# 05_-_AUDIO.net
KiCad netlist of a schematic drawn in Altium Designer
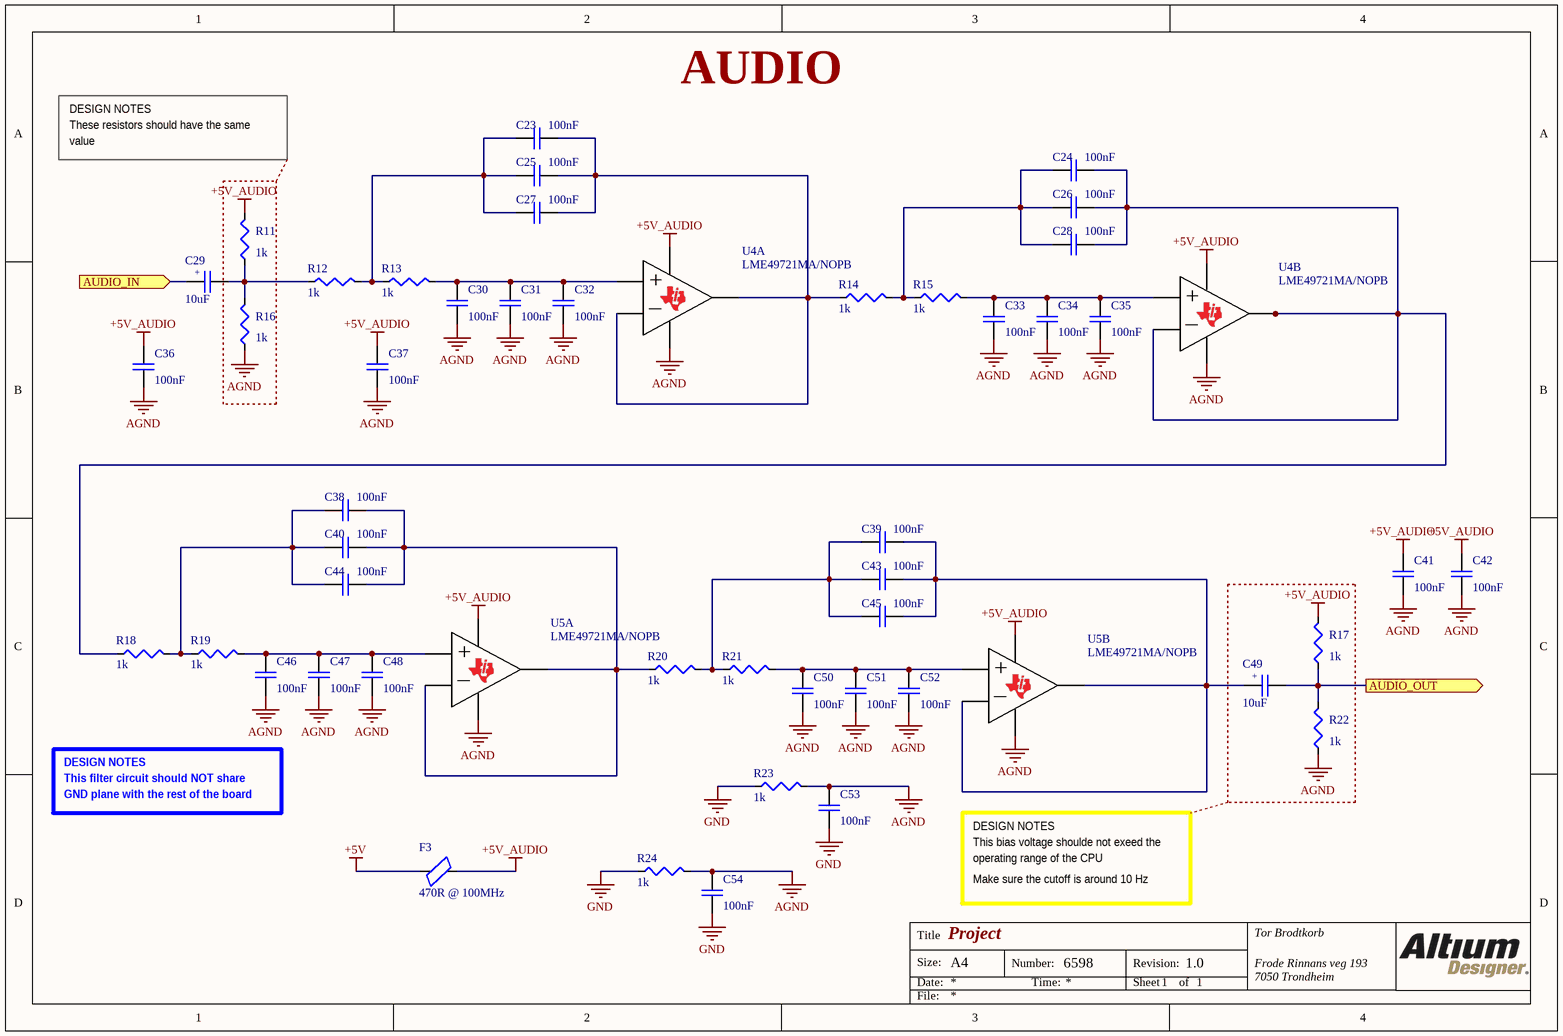
[diagram p0: [05] - AUDIO.SchDoc]

(export (version "E")
  (design (tool "Eeschema 10.0.6"))
  (components
    (comp (ref "C23")
      (value "100nF")
      (footprint "C0603")
      (description "C0603")
      (fields (field (name "Comment") "02016D104KAT2A"))
      (libsource (lib "Passive components") (part "02016D104KAT2A"))
    )
    (comp (ref "C24")
      (value "100nF")
      (footprint "C0603")
      (description "C0603")
      (fields (field (name "Comment") "02016D104KAT2A"))
      (libsource (lib "Passive components") (part "02016D104KAT2A"))
    )
    (comp (ref "C25")
      (value "100nF")
      (footprint "C0603")
      (description "C0603")
      (fields (field (name "Comment") "02016D104KAT2A"))
      (libsource (lib "Passive components") (part "02016D104KAT2A"))
    )
    (comp (ref "C26")
      (value "100nF")
      (footprint "C0603")
      (description "C0603")
      (fields (field (name "Comment") "02016D104KAT2A"))
      (libsource (lib "Passive components") (part "02016D104KAT2A"))
    )
    (comp (ref "C27")
      (value "100nF")
      (footprint "C0603")
      (description "C0603")
      (fields (field (name "Comment") "02016D104KAT2A"))
      (libsource (lib "Passive components") (part "02016D104KAT2A"))
    )
    (comp (ref "C28")
      (value "100nF")
      (footprint "C0603")
      (description "C0603")
      (fields (field (name "Comment") "02016D104KAT2A"))
      (libsource (lib "Passive components") (part "02016D104KAT2A"))
    )
    (comp (ref "C29")
      (value "10uF")
      (footprint "Capacitor electrolytic SMD 4x5.4")
      (description "El. Capacitor SMD 4x5.4")
      (fields (field (name "Comment") "EEE1HA2R2SR"))
      (libsource (lib "Passive components") (part "EEE1HA2R2SR"))
    )
    (comp (ref "C30")
      (value "100nF")
      (footprint "C0603")
      (description "C0603")
      (fields (field (name "Comment") "02016D104KAT2A"))
      (libsource (lib "Passive components") (part "02016D104KAT2A"))
    )
    (comp (ref "C31")
      (value "100nF")
      (footprint "C0603")
      (description "C0603")
      (fields (field (name "Comment") "02016D104KAT2A"))
      (libsource (lib "Passive components") (part "02016D104KAT2A"))
    )
    (comp (ref "C32")
      (value "100nF")
      (footprint "C0603")
      (description "C0603")
      (fields (field (name "Comment") "02016D104KAT2A"))
      (libsource (lib "Passive components") (part "02016D104KAT2A"))
    )
    (comp (ref "C33")
      (value "100nF")
      (footprint "C0603")
      (description "C0603")
      (fields (field (name "Comment") "02016D104KAT2A"))
      (libsource (lib "Passive components") (part "02016D104KAT2A"))
    )
    (comp (ref "C34")
      (value "100nF")
      (footprint "C0603")
      (description "C0603")
      (fields (field (name "Comment") "02016D104KAT2A"))
      (libsource (lib "Passive components") (part "02016D104KAT2A"))
    )
    (comp (ref "C35")
      (value "100nF")
      (footprint "C0603")
      (description "C0603")
      (fields (field (name "Comment") "02016D104KAT2A"))
      (libsource (lib "Passive components") (part "02016D104KAT2A"))
    )
    (comp (ref "C36")
      (value "100nF")
      (footprint "C0603")
      (description "C0603")
      (fields (field (name "Comment") "02016D104KAT2A"))
      (libsource (lib "Passive components") (part "02016D104KAT2A"))
    )
    (comp (ref "C37")
      (value "100nF")
      (footprint "C0603")
      (description "C0603")
      (fields (field (name "Comment") "02016D104KAT2A"))
      (libsource (lib "Passive components") (part "02016D104KAT2A"))
    )
    (comp (ref "C38")
      (value "100nF")
      (footprint "C0603")
      (description "C0603")
      (fields (field (name "Comment") "02016D104KAT2A"))
      (libsource (lib "Passive components") (part "02016D104KAT2A"))
    )
    (comp (ref "C39")
      (value "100nF")
      (footprint "C0603")
      (description "C0603")
      (fields (field (name "Comment") "02016D104KAT2A"))
      (libsource (lib "Passive components") (part "02016D104KAT2A"))
    )
    (comp (ref "C40")
      (value "100nF")
      (footprint "C0603")
      (description "C0603")
      (fields (field (name "Comment") "02016D104KAT2A"))
      (libsource (lib "Passive components") (part "02016D104KAT2A"))
    )
    (comp (ref "C41")
      (value "100nF")
      (footprint "C0603")
      (description "C0603")
      (fields (field (name "Comment") "02016D104KAT2A"))
      (libsource (lib "Passive components") (part "02016D104KAT2A"))
    )
    (comp (ref "C42")
      (value "100nF")
      (footprint "C0603")
      (description "C0603")
      (fields (field (name "Comment") "02016D104KAT2A"))
      (libsource (lib "Passive components") (part "02016D104KAT2A"))
    )
    (comp (ref "C43")
      (value "100nF")
      (footprint "C0603")
      (description "C0603")
      (fields (field (name "Comment") "02016D104KAT2A"))
      (libsource (lib "Passive components") (part "02016D104KAT2A"))
    )
    (comp (ref "C44")
      (value "100nF")
      (footprint "C0603")
      (description "C0603")
      (fields (field (name "Comment") "02016D104KAT2A"))
      (libsource (lib "Passive components") (part "02016D104KAT2A"))
    )
    (comp (ref "C45")
      (value "100nF")
      (footprint "C0603")
      (description "C0603")
      (fields (field (name "Comment") "02016D104KAT2A"))
      (libsource (lib "Passive components") (part "02016D104KAT2A"))
    )
    (comp (ref "C46")
      (value "100nF")
      (footprint "C0603")
      (description "C0603")
      (fields (field (name "Comment") "02016D104KAT2A"))
      (libsource (lib "Passive components") (part "02016D104KAT2A"))
    )
    (comp (ref "C47")
      (value "100nF")
      (footprint "C0603")
      (description "C0603")
      (fields (field (name "Comment") "02016D104KAT2A"))
      (libsource (lib "Passive components") (part "02016D104KAT2A"))
    )
    (comp (ref "C48")
      (value "100nF")
      (footprint "C0603")
      (description "C0603")
      (fields (field (name "Comment") "02016D104KAT2A"))
      (libsource (lib "Passive components") (part "02016D104KAT2A"))
    )
    (comp (ref "C49")
      (value "10uF")
      (footprint "Capacitor electrolytic SMD 4x5.4")
      (description "El. Capacitor SMD 4x5.4")
      (fields (field (name "Comment") "EEE1HA2R2SR"))
      (libsource (lib "Passive components") (part "EEE1HA2R2SR"))
    )
    (comp (ref "C50")
      (value "100nF")
      (footprint "C0603")
      (description "C0603")
      (fields (field (name "Comment") "02016D104KAT2A"))
      (libsource (lib "Passive components") (part "02016D104KAT2A"))
    )
    (comp (ref "C51")
      (value "100nF")
      (footprint "C0603")
      (description "C0603")
      (fields (field (name "Comment") "02016D104KAT2A"))
      (libsource (lib "Passive components") (part "02016D104KAT2A"))
    )
    (comp (ref "C52")
      (value "100nF")
      (footprint "C0603")
      (description "C0603")
      (fields (field (name "Comment") "02016D104KAT2A"))
      (libsource (lib "Passive components") (part "02016D104KAT2A"))
    )
    (comp (ref "C53")
      (value "100nF")
      (footprint "C0603")
      (description "C0603")
      (fields (field (name "Comment") "02016D104KAT2A"))
      (libsource (lib "Passive components") (part "02016D104KAT2A"))
    )
    (comp (ref "C54")
      (value "100nF")
      (footprint "C0603")
      (description "C0603")
      (fields (field (name "Comment") "02016D104KAT2A"))
      (libsource (lib "Passive components") (part "02016D104KAT2A"))
    )
    (comp (ref "F3")
      (value "470R @ 100MHz")
      (footprint "Ferrite bead 0603")
      (description "Ferrite bead 0603")
      (fields (field (name "Comment") "BLM18AG121SN1D"))
      (libsource (lib "Passive components") (part "BLM18AG121SN1D"))
    )
    (comp (ref "R11")
      (value "1k")
      (footprint "R0603")
      (description "R0603")
      (fields (field (name "Comment") "CPF-A-0603B100KE1"))
      (libsource (lib "Passive components") (part "CPF-A-0603B100KE1"))
    )
    (comp (ref "R12")
      (value "1k")
      (footprint "R0603")
      (description "R0603")
      (fields (field (name "Comment") "CPF-A-0603B100KE1"))
      (libsource (lib "Passive components") (part "CPF-A-0603B100KE1"))
    )
    (comp (ref "R13")
      (value "1k")
      (footprint "R0603")
      (description "R0603")
      (fields (field (name "Comment") "CPF-A-0603B100KE1"))
      (libsource (lib "Passive components") (part "CPF-A-0603B100KE1"))
    )
    (comp (ref "R14")
      (value "1k")
      (footprint "R0603")
      (description "R0603")
      (fields (field (name "Comment") "CPF-A-0603B100KE1"))
      (libsource (lib "Passive components") (part "CPF-A-0603B100KE1"))
    )
    (comp (ref "R15")
      (value "1k")
      (footprint "R0603")
      (description "R0603")
      (fields (field (name "Comment") "CPF-A-0603B100KE1"))
      (libsource (lib "Passive components") (part "CPF-A-0603B100KE1"))
    )
    (comp (ref "R16")
      (value "1k")
      (footprint "R0603")
      (description "R0603")
      (fields (field (name "Comment") "CPF-A-0603B100KE1"))
      (libsource (lib "Passive components") (part "CPF-A-0603B100KE1"))
    )
    (comp (ref "R17")
      (value "1k")
      (footprint "R0603")
      (description "R0603")
      (fields (field (name "Comment") "CPF-A-0603B100KE1"))
      (libsource (lib "Passive components") (part "CPF-A-0603B100KE1"))
    )
    (comp (ref "R18")
      (value "1k")
      (footprint "R0603")
      (description "R0603")
      (fields (field (name "Comment") "CPF-A-0603B100KE1"))
      (libsource (lib "Passive components") (part "CPF-A-0603B100KE1"))
    )
    (comp (ref "R19")
      (value "1k")
      (footprint "R0603")
      (description "R0603")
      (fields (field (name "Comment") "CPF-A-0603B100KE1"))
      (libsource (lib "Passive components") (part "CPF-A-0603B100KE1"))
    )
    (comp (ref "R20")
      (value "1k")
      (footprint "R0603")
      (description "R0603")
      (fields (field (name "Comment") "CPF-A-0603B100KE1"))
      (libsource (lib "Passive components") (part "CPF-A-0603B100KE1"))
    )
    (comp (ref "R21")
      (value "1k")
      (footprint "R0603")
      (description "R0603")
      (fields (field (name "Comment") "CPF-A-0603B100KE1"))
      (libsource (lib "Passive components") (part "CPF-A-0603B100KE1"))
    )
    (comp (ref "R22")
      (value "1k")
      (footprint "R0603")
      (description "R0603")
      (fields (field (name "Comment") "CPF-A-0603B100KE1"))
      (libsource (lib "Passive components") (part "CPF-A-0603B100KE1"))
    )
    (comp (ref "R23")
      (value "1k")
      (footprint "R0603")
      (description "R0603")
      (fields (field (name "Comment") "CPF-A-0603B100KE1"))
      (libsource (lib "Passive components") (part "CPF-A-0603B100KE1"))
    )
    (comp (ref "R24")
      (value "1k")
      (footprint "R0603")
      (description "R0603")
      (fields (field (name "Comment") "CPF-A-0603B100KE1"))
      (libsource (lib "Passive components") (part "CPF-A-0603B100KE1"))
    )
    (comp (ref "U4")
      (value "LME49721MA/NOPB")
      (footprint "LME49721MA/NOPB")
      (description "Audio OP amp, single supply, low voltage")
      (libsource (lib "IC") (part "LME49721MA/NOPB"))
    )
    (comp (ref "U5")
      (value "LME49721MA/NOPB")
      (footprint "LME49721MA/NOPB")
      (description "Audio OP amp, single supply, low voltage")
      (libsource (lib "IC") (part "LME49721MA/NOPB"))
    )
  )
  (nets
    (net (code "1") (name "+5V") (class "Default")
      (node (ref "F3") (pin "1") (pinfunction "1_1") (pintype "passive"))
    )
    (net (code "2") (name "+5V_AUDIO") (class "Default")
      (node (ref "C36") (pin "2") (pinfunction "2_2") (pintype "passive"))
      (node (ref "C37") (pin "2") (pinfunction "2_2") (pintype "passive"))
      (node (ref "C41") (pin "2") (pinfunction "2_2") (pintype "passive"))
      (node (ref "C42") (pin "2") (pinfunction "2_2") (pintype "passive"))
      (node (ref "F3") (pin "2") (pinfunction "2_2") (pintype "passive"))
      (node (ref "R11") (pin "2") (pinfunction "2_2") (pintype "passive"))
      (node (ref "R17") (pin "2") (pinfunction "2_2") (pintype "passive"))
      (node (ref "U4") (pin "8") (pinfunction "VDD_8") (pintype "passive"))
      (node (ref "U5") (pin "8") (pinfunction "VDD_8") (pintype "passive"))
    )
    (net (code "3") (name "/AUDIO_IN") (class "Default")
      (node (ref "C29") (pin "1") (pinfunction "1_1") (pintype "passive"))
    )
    (net (code "4") (name "/AUDIO_OUT") (class "Default")
      (node (ref "C49") (pin "2") (pinfunction "2_2") (pintype "passive"))
      (node (ref "R17") (pin "1") (pinfunction "1_1") (pintype "passive"))
      (node (ref "R22") (pin "2") (pinfunction "2_2") (pintype "passive"))
    )
    (net (code "5") (name "AGND") (class "Default")
      (node (ref "C30") (pin "1") (pinfunction "1_1") (pintype "passive"))
      (node (ref "C31") (pin "1") (pinfunction "1_1") (pintype "passive"))
      (node (ref "C32") (pin "1") (pinfunction "1_1") (pintype "passive"))
      (node (ref "C33") (pin "1") (pinfunction "1_1") (pintype "passive"))
      (node (ref "C34") (pin "1") (pinfunction "1_1") (pintype "passive"))
      (node (ref "C35") (pin "1") (pinfunction "1_1") (pintype "passive"))
      (node (ref "C36") (pin "1") (pinfunction "1_1") (pintype "passive"))
      (node (ref "C37") (pin "1") (pinfunction "1_1") (pintype "passive"))
      (node (ref "C41") (pin "1") (pinfunction "1_1") (pintype "passive"))
      (node (ref "C42") (pin "1") (pinfunction "1_1") (pintype "passive"))
      (node (ref "C46") (pin "1") (pinfunction "1_1") (pintype "passive"))
      (node (ref "C47") (pin "1") (pinfunction "1_1") (pintype "passive"))
      (node (ref "C48") (pin "1") (pinfunction "1_1") (pintype "passive"))
      (node (ref "C50") (pin "1") (pinfunction "1_1") (pintype "passive"))
      (node (ref "C51") (pin "1") (pinfunction "1_1") (pintype "passive"))
      (node (ref "C52") (pin "1") (pinfunction "1_1") (pintype "passive"))
      (node (ref "C53") (pin "2") (pinfunction "2_2") (pintype "passive"))
      (node (ref "C54") (pin "2") (pinfunction "2_2") (pintype "passive"))
      (node (ref "R16") (pin "1") (pinfunction "1_1") (pintype "passive"))
      (node (ref "R22") (pin "1") (pinfunction "1_1") (pintype "passive"))
      (node (ref "R23") (pin "2") (pinfunction "2_2") (pintype "passive"))
      (node (ref "R24") (pin "2") (pinfunction "2_2") (pintype "passive"))
      (node (ref "U4") (pin "4") (pinfunction "VDD_4") (pintype "passive"))
      (node (ref "U5") (pin "4") (pinfunction "VDD_4") (pintype "passive"))
    )
    (net (code "6") (name "GND") (class "Default")
      (node (ref "C53") (pin "1") (pinfunction "1_1") (pintype "passive"))
      (node (ref "C54") (pin "1") (pinfunction "1_1") (pintype "passive"))
      (node (ref "R23") (pin "1") (pinfunction "1_1") (pintype "passive"))
      (node (ref "R24") (pin "1") (pinfunction "1_1") (pintype "passive"))
    )
    (net (code "7") (name "Net-(C23-Pad1)") (class "Default")
      (node (ref "C23") (pin "1") (pinfunction "1_1") (pintype "passive"))
      (node (ref "C25") (pin "1") (pinfunction "1_1") (pintype "passive"))
      (node (ref "C27") (pin "1") (pinfunction "1_1") (pintype "passive"))
      (node (ref "R12") (pin "2") (pinfunction "2_2") (pintype "passive"))
      (node (ref "R13") (pin "1") (pinfunction "1_1") (pintype "passive"))
    )
    (net (code "8") (name "Net-(C23-Pad2)") (class "Default")
      (node (ref "C23") (pin "2") (pinfunction "2_2") (pintype "passive"))
      (node (ref "C25") (pin "2") (pinfunction "2_2") (pintype "passive"))
      (node (ref "C27") (pin "2") (pinfunction "2_2") (pintype "passive"))
      (node (ref "R14") (pin "1") (pinfunction "1_1") (pintype "passive"))
      (node (ref "U4") (pin "1") (pinfunction "VDD_1") (pintype "passive"))
      (node (ref "U4") (pin "2") (pinfunction "VDD_2") (pintype "passive"))
    )
    (net (code "9") (name "Net-(C24-Pad1)") (class "Default")
      (node (ref "C24") (pin "1") (pinfunction "1_1") (pintype "passive"))
      (node (ref "C26") (pin "1") (pinfunction "1_1") (pintype "passive"))
      (node (ref "C28") (pin "1") (pinfunction "1_1") (pintype "passive"))
      (node (ref "R14") (pin "2") (pinfunction "2_2") (pintype "passive"))
      (node (ref "R15") (pin "1") (pinfunction "1_1") (pintype "passive"))
    )
    (net (code "10") (name "Net-(C24-Pad2)") (class "Default")
      (node (ref "C24") (pin "2") (pinfunction "2_2") (pintype "passive"))
      (node (ref "C26") (pin "2") (pinfunction "2_2") (pintype "passive"))
      (node (ref "C28") (pin "2") (pinfunction "2_2") (pintype "passive"))
      (node (ref "R18") (pin "1") (pinfunction "1_1") (pintype "passive"))
      (node (ref "U4") (pin "6") (pinfunction "VDD_6") (pintype "passive"))
      (node (ref "U4") (pin "7") (pinfunction "VDD_7") (pintype "passive"))
    )
    (net (code "11") (name "Net-(C29-Pad2)") (class "Default")
      (node (ref "C29") (pin "2") (pinfunction "2_2") (pintype "passive"))
      (node (ref "R11") (pin "1") (pinfunction "1_1") (pintype "passive"))
      (node (ref "R12") (pin "1") (pinfunction "1_1") (pintype "passive"))
      (node (ref "R16") (pin "2") (pinfunction "2_2") (pintype "passive"))
    )
    (net (code "12") (name "Net-(C30-Pad2)") (class "Default")
      (node (ref "C30") (pin "2") (pinfunction "2_2") (pintype "passive"))
      (node (ref "C31") (pin "2") (pinfunction "2_2") (pintype "passive"))
      (node (ref "C32") (pin "2") (pinfunction "2_2") (pintype "passive"))
      (node (ref "R13") (pin "2") (pinfunction "2_2") (pintype "passive"))
      (node (ref "U4") (pin "3") (pinfunction "VDD_3") (pintype "passive"))
    )
    (net (code "13") (name "Net-(C33-Pad2)") (class "Default")
      (node (ref "C33") (pin "2") (pinfunction "2_2") (pintype "passive"))
      (node (ref "C34") (pin "2") (pinfunction "2_2") (pintype "passive"))
      (node (ref "C35") (pin "2") (pinfunction "2_2") (pintype "passive"))
      (node (ref "R15") (pin "2") (pinfunction "2_2") (pintype "passive"))
      (node (ref "U4") (pin "5") (pinfunction "VDD_5") (pintype "passive"))
    )
    (net (code "14") (name "Net-(C38-Pad1)") (class "Default")
      (node (ref "C38") (pin "1") (pinfunction "1_1") (pintype "passive"))
      (node (ref "C40") (pin "1") (pinfunction "1_1") (pintype "passive"))
      (node (ref "C44") (pin "1") (pinfunction "1_1") (pintype "passive"))
      (node (ref "R18") (pin "2") (pinfunction "2_2") (pintype "passive"))
      (node (ref "R19") (pin "1") (pinfunction "1_1") (pintype "passive"))
    )
    (net (code "15") (name "Net-(C38-Pad2)") (class "Default")
      (node (ref "C38") (pin "2") (pinfunction "2_2") (pintype "passive"))
      (node (ref "C40") (pin "2") (pinfunction "2_2") (pintype "passive"))
      (node (ref "C44") (pin "2") (pinfunction "2_2") (pintype "passive"))
      (node (ref "R20") (pin "1") (pinfunction "1_1") (pintype "passive"))
      (node (ref "U5") (pin "1") (pinfunction "VDD_1") (pintype "passive"))
      (node (ref "U5") (pin "2") (pinfunction "VDD_2") (pintype "passive"))
    )
    (net (code "16") (name "Net-(C39-Pad1)") (class "Default")
      (node (ref "C39") (pin "1") (pinfunction "1_1") (pintype "passive"))
      (node (ref "C43") (pin "1") (pinfunction "1_1") (pintype "passive"))
      (node (ref "C45") (pin "1") (pinfunction "1_1") (pintype "passive"))
      (node (ref "R20") (pin "2") (pinfunction "2_2") (pintype "passive"))
      (node (ref "R21") (pin "1") (pinfunction "1_1") (pintype "passive"))
    )
    (net (code "17") (name "Net-(C39-Pad2)") (class "Default")
      (node (ref "C39") (pin "2") (pinfunction "2_2") (pintype "passive"))
      (node (ref "C43") (pin "2") (pinfunction "2_2") (pintype "passive"))
      (node (ref "C45") (pin "2") (pinfunction "2_2") (pintype "passive"))
      (node (ref "C49") (pin "1") (pinfunction "1_1") (pintype "passive"))
      (node (ref "U5") (pin "6") (pinfunction "VDD_6") (pintype "passive"))
      (node (ref "U5") (pin "7") (pinfunction "VDD_7") (pintype "passive"))
    )
    (net (code "18") (name "Net-(C46-Pad2)") (class "Default")
      (node (ref "C46") (pin "2") (pinfunction "2_2") (pintype "passive"))
      (node (ref "C47") (pin "2") (pinfunction "2_2") (pintype "passive"))
      (node (ref "C48") (pin "2") (pinfunction "2_2") (pintype "passive"))
      (node (ref "R19") (pin "2") (pinfunction "2_2") (pintype "passive"))
      (node (ref "U5") (pin "3") (pinfunction "VDD_3") (pintype "passive"))
    )
    (net (code "19") (name "Net-(C50-Pad2)") (class "Default")
      (node (ref "C50") (pin "2") (pinfunction "2_2") (pintype "passive"))
      (node (ref "C51") (pin "2") (pinfunction "2_2") (pintype "passive"))
      (node (ref "C52") (pin "2") (pinfunction "2_2") (pintype "passive"))
      (node (ref "R21") (pin "2") (pinfunction "2_2") (pintype "passive"))
      (node (ref "U5") (pin "5") (pinfunction "VDD_5") (pintype "passive"))
    )
  )
)
